# schematics.net
KiCad netlist of a schematic drawn in EasyEDA
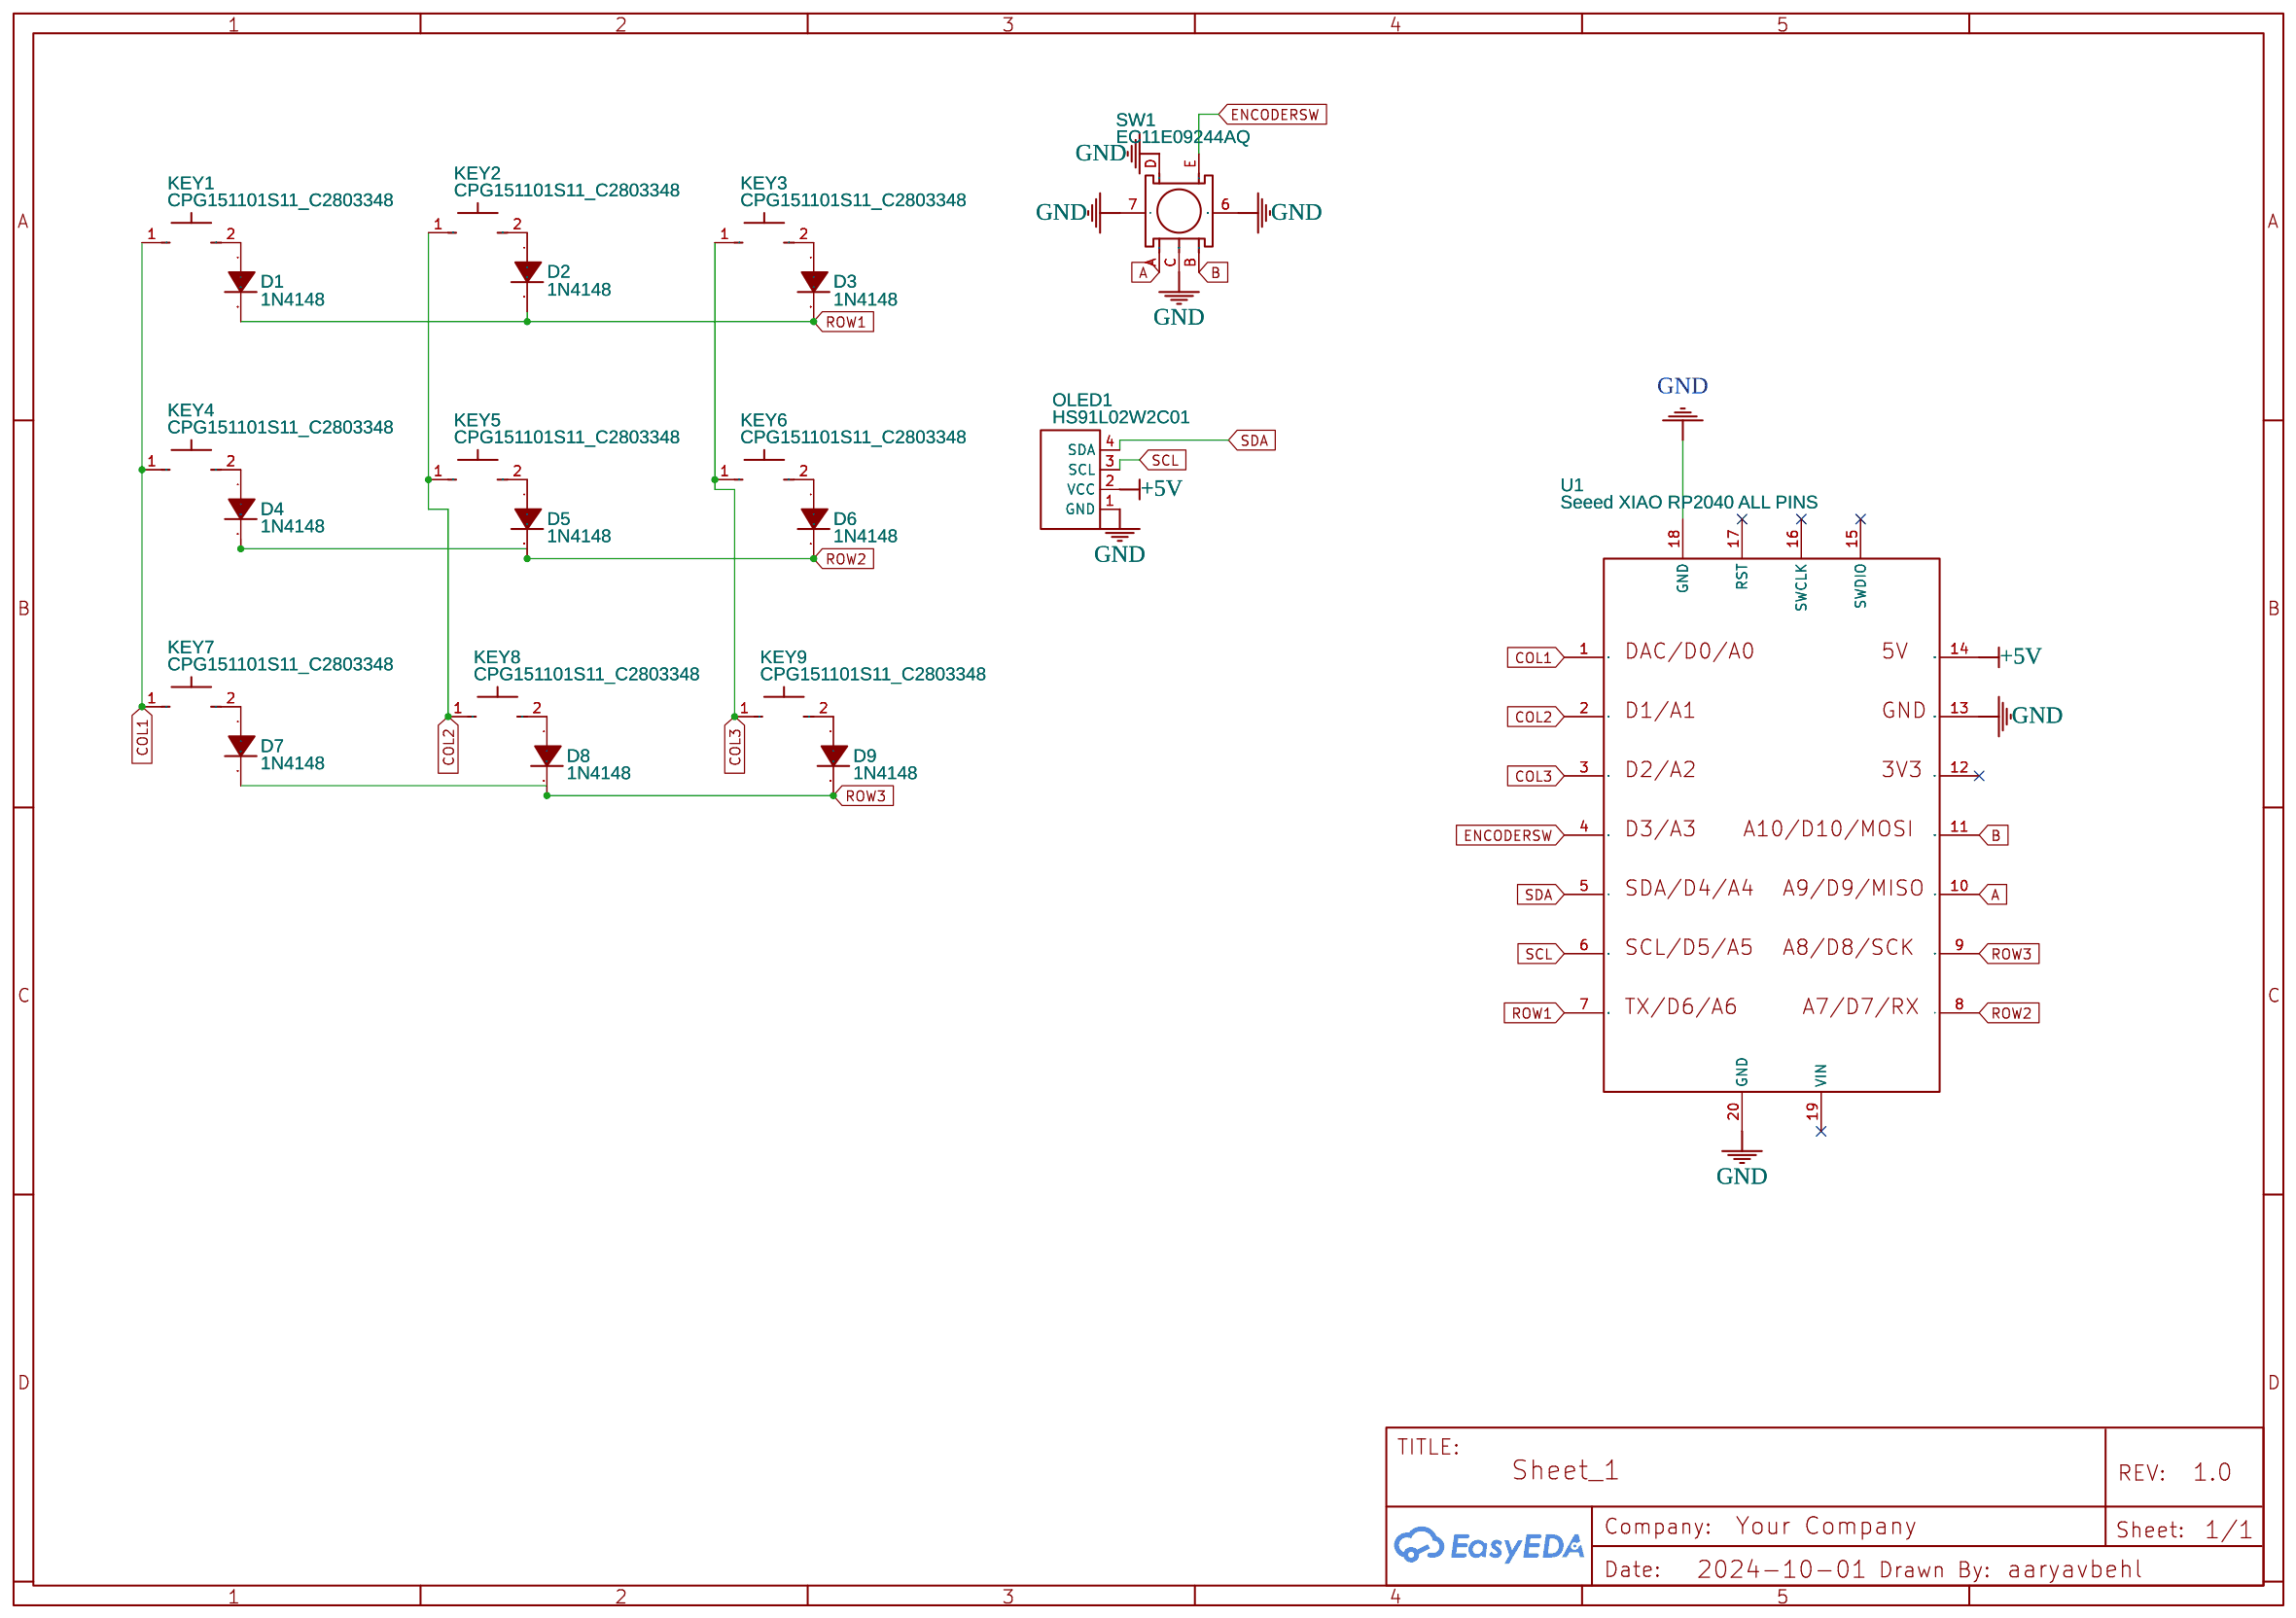
[diagram p0: schematic sheet]

(export (version "E")
  (design (tool "Eeschema 10.0.6"))
  (components
    (comp (ref "D1")
      (value "1N4148")
      (fields (field (name "Manufacturer") "ST(先科)"))
      (libsource (lib "") (part "1N4148"))
    )
    (comp (ref "D2")
      (value "1N4148")
      (fields (field (name "Manufacturer") "ST(先科)"))
      (libsource (lib "") (part "1N4148"))
    )
    (comp (ref "D3")
      (value "1N4148")
      (fields (field (name "Manufacturer") "ST(先科)"))
      (libsource (lib "") (part "1N4148"))
    )
    (comp (ref "D4")
      (value "1N4148")
      (fields (field (name "Manufacturer") "ST(先科)"))
      (libsource (lib "") (part "1N4148"))
    )
    (comp (ref "D5")
      (value "1N4148")
      (fields (field (name "Manufacturer") "ST(先科)"))
      (libsource (lib "") (part "1N4148"))
    )
    (comp (ref "D6")
      (value "1N4148")
      (fields (field (name "Manufacturer") "ST(先科)"))
      (libsource (lib "") (part "1N4148"))
    )
    (comp (ref "D7")
      (value "1N4148")
      (fields (field (name "Manufacturer") "ST(先科)"))
      (libsource (lib "") (part "1N4148"))
    )
    (comp (ref "D8")
      (value "1N4148")
      (fields (field (name "Manufacturer") "ST(先科)"))
      (libsource (lib "") (part "1N4148"))
    )
    (comp (ref "D9")
      (value "1N4148")
      (fields (field (name "Manufacturer") "ST(先科)"))
      (libsource (lib "") (part "1N4148"))
    )
    (comp (ref "KEY1")
      (value "CPG151101S11_C2803348")
      (fields (field (name "Manufacturer Part") "CPG151101S11") (field (name "Manufacturer") "Kailh(凯华)"))
      (libsource (lib "") (part "CPG151101S11_C2803348"))
    )
    (comp (ref "KEY2")
      (value "CPG151101S11_C2803348")
      (fields (field (name "Manufacturer Part") "CPG151101S11") (field (name "Manufacturer") "Kailh(凯华)"))
      (libsource (lib "") (part "CPG151101S11_C2803348"))
    )
    (comp (ref "KEY3")
      (value "CPG151101S11_C2803348")
      (fields (field (name "Manufacturer Part") "CPG151101S11") (field (name "Manufacturer") "Kailh(凯华)"))
      (libsource (lib "") (part "CPG151101S11_C2803348"))
    )
    (comp (ref "KEY4")
      (value "CPG151101S11_C2803348")
      (fields (field (name "Manufacturer Part") "CPG151101S11") (field (name "Manufacturer") "Kailh(凯华)"))
      (libsource (lib "") (part "CPG151101S11_C2803348"))
    )
    (comp (ref "KEY5")
      (value "CPG151101S11_C2803348")
      (fields (field (name "Manufacturer Part") "CPG151101S11") (field (name "Manufacturer") "Kailh(凯华)"))
      (libsource (lib "") (part "CPG151101S11_C2803348"))
    )
    (comp (ref "KEY6")
      (value "CPG151101S11_C2803348")
      (fields (field (name "Manufacturer Part") "CPG151101S11") (field (name "Manufacturer") "Kailh(凯华)"))
      (libsource (lib "") (part "CPG151101S11_C2803348"))
    )
    (comp (ref "KEY7")
      (value "CPG151101S11_C2803348")
      (fields (field (name "Manufacturer Part") "CPG151101S11") (field (name "Manufacturer") "Kailh(凯华)"))
      (libsource (lib "") (part "CPG151101S11_C2803348"))
    )
    (comp (ref "KEY8")
      (value "CPG151101S11_C2803348")
      (fields (field (name "Manufacturer Part") "CPG151101S11") (field (name "Manufacturer") "Kailh(凯华)"))
      (libsource (lib "") (part "CPG151101S11_C2803348"))
    )
    (comp (ref "KEY9")
      (value "CPG151101S11_C2803348")
      (fields (field (name "Manufacturer Part") "CPG151101S11") (field (name "Manufacturer") "Kailh(凯华)"))
      (libsource (lib "") (part "CPG151101S11_C2803348"))
    )
    (comp (ref "OLED1")
      (value "HS91L02W2C01")
      (fields (field (name "Manufacturer") "HS(汉昇)"))
      (libsource (lib "") (part "HS91L02W2C01"))
    )
    (comp (ref "SW1")
      (value "EC11E09244AQ")
      (fields (field (name "Manufacturer") "ALPSALPINE(阿尔卑斯阿尔派)"))
      (libsource (lib "") (part "EC11E09244AQ"))
    )
    (comp (ref "U1")
      (value "Seeed XIAO RP2040 ALL PINS")
      (fields (field (name "Manufacturer Part") "102010328") (field (name "Manufacturer") "Seeedstudio"))
      (libsource (lib "") (part "Seeed XIAO RP2040 ALL PINS"))
    )
  )
  (nets
    (net (code "1") (name "+5V") (class "Default")
      (node (ref "OLED1") (pin "2") (pinfunction "VCC_2") (pintype "unspecified"))
      (node (ref "U1") (pin "14") (pinfunction "13_14") (pintype "unspecified"))
    )
    (net (code "2") (name "A") (class "Default")
      (node (ref "SW1") (pin "A") (pinfunction "A_A") (pintype "unspecified"))
      (node (ref "U1") (pin "10") (pinfunction "9_10") (pintype "unspecified"))
    )
    (net (code "3") (name "B") (class "Default")
      (node (ref "SW1") (pin "B") (pinfunction "B_B") (pintype "unspecified"))
      (node (ref "U1") (pin "11") (pinfunction "10_11") (pintype "unspecified"))
    )
    (net (code "4") (name "COL1") (class "Default")
      (node (ref "KEY1") (pin "1") (pinfunction "1_1") (pintype "input"))
      (node (ref "KEY4") (pin "1") (pinfunction "1_1") (pintype "input"))
      (node (ref "KEY7") (pin "1") (pinfunction "1_1") (pintype "input"))
      (node (ref "U1") (pin "1") (pinfunction "0_1") (pintype "unspecified"))
    )
    (net (code "5") (name "COL2") (class "Default")
      (node (ref "KEY2") (pin "1") (pinfunction "1_1") (pintype "input"))
      (node (ref "KEY5") (pin "1") (pinfunction "1_1") (pintype "input"))
      (node (ref "KEY8") (pin "1") (pinfunction "1_1") (pintype "input"))
      (node (ref "U1") (pin "2") (pinfunction "1_2") (pintype "unspecified"))
    )
    (net (code "6") (name "COL3") (class "Default")
      (node (ref "KEY3") (pin "1") (pinfunction "1_1") (pintype "input"))
      (node (ref "KEY6") (pin "1") (pinfunction "1_1") (pintype "input"))
      (node (ref "KEY9") (pin "1") (pinfunction "1_1") (pintype "input"))
      (node (ref "U1") (pin "3") (pinfunction "2_3") (pintype "unspecified"))
    )
    (net (code "7") (name "ENCODERSW") (class "Default")
      (node (ref "SW1") (pin "E") (pinfunction "E_E") (pintype "unspecified"))
      (node (ref "U1") (pin "4") (pinfunction "3_4") (pintype "unspecified"))
    )
    (net (code "8") (name "GND") (class "Default")
      (node (ref "OLED1") (pin "1") (pinfunction "GND_1") (pintype "unspecified"))
      (node (ref "SW1") (pin "6") (pinfunction "6_6") (pintype "unspecified"))
      (node (ref "SW1") (pin "7") (pinfunction "7_7") (pintype "unspecified"))
      (node (ref "SW1") (pin "C") (pinfunction "C_C") (pintype "unspecified"))
      (node (ref "SW1") (pin "D") (pinfunction "D_D") (pintype "unspecified"))
      (node (ref "U1") (pin "13") (pinfunction "12_13") (pintype "unspecified"))
      (node (ref "U1") (pin "18") (pinfunction "GND_18") (pintype "unspecified"))
      (node (ref "U1") (pin "20") (pinfunction "GND_20") (pintype "unspecified"))
    )
    (net (code "9") (name "Net-(D1-A)") (class "Default")
      (node (ref "D1") (pin "1") (pinfunction "A_1") (pintype "unspecified"))
      (node (ref "KEY1") (pin "2") (pinfunction "2_2") (pintype "input"))
    )
    (net (code "10") (name "Net-(D2-A)") (class "Default")
      (node (ref "D2") (pin "1") (pinfunction "A_1") (pintype "unspecified"))
      (node (ref "KEY2") (pin "2") (pinfunction "2_2") (pintype "input"))
    )
    (net (code "11") (name "Net-(D3-A)") (class "Default")
      (node (ref "D3") (pin "1") (pinfunction "A_1") (pintype "unspecified"))
      (node (ref "KEY3") (pin "2") (pinfunction "2_2") (pintype "input"))
    )
    (net (code "12") (name "Net-(D4-A)") (class "Default")
      (node (ref "D4") (pin "1") (pinfunction "A_1") (pintype "unspecified"))
      (node (ref "KEY4") (pin "2") (pinfunction "2_2") (pintype "input"))
    )
    (net (code "13") (name "Net-(D5-A)") (class "Default")
      (node (ref "D5") (pin "1") (pinfunction "A_1") (pintype "unspecified"))
      (node (ref "KEY5") (pin "2") (pinfunction "2_2") (pintype "input"))
    )
    (net (code "14") (name "Net-(D6-A)") (class "Default")
      (node (ref "D6") (pin "1") (pinfunction "A_1") (pintype "unspecified"))
      (node (ref "KEY6") (pin "2") (pinfunction "2_2") (pintype "input"))
    )
    (net (code "15") (name "Net-(D7-A)") (class "Default")
      (node (ref "D7") (pin "1") (pinfunction "A_1") (pintype "unspecified"))
      (node (ref "KEY7") (pin "2") (pinfunction "2_2") (pintype "input"))
    )
    (net (code "16") (name "Net-(D8-A)") (class "Default")
      (node (ref "D8") (pin "1") (pinfunction "A_1") (pintype "unspecified"))
      (node (ref "KEY8") (pin "2") (pinfunction "2_2") (pintype "input"))
    )
    (net (code "17") (name "Net-(D9-A)") (class "Default")
      (node (ref "D9") (pin "1") (pinfunction "A_1") (pintype "unspecified"))
      (node (ref "KEY9") (pin "2") (pinfunction "2_2") (pintype "input"))
    )
    (net (code "18") (name "ROW1") (class "Default")
      (node (ref "D1") (pin "2") (pinfunction "C_2") (pintype "unspecified"))
      (node (ref "D2") (pin "2") (pinfunction "C_2") (pintype "unspecified"))
      (node (ref "D3") (pin "2") (pinfunction "C_2") (pintype "unspecified"))
      (node (ref "U1") (pin "7") (pinfunction "6_7") (pintype "unspecified"))
    )
    (net (code "19") (name "ROW2") (class "Default")
      (node (ref "D4") (pin "2") (pinfunction "C_2") (pintype "unspecified"))
      (node (ref "D5") (pin "2") (pinfunction "C_2") (pintype "unspecified"))
      (node (ref "D6") (pin "2") (pinfunction "C_2") (pintype "unspecified"))
      (node (ref "U1") (pin "8") (pinfunction "7_8") (pintype "unspecified"))
    )
    (net (code "20") (name "ROW3") (class "Default")
      (node (ref "D7") (pin "2") (pinfunction "C_2") (pintype "unspecified"))
      (node (ref "D8") (pin "2") (pinfunction "C_2") (pintype "unspecified"))
      (node (ref "D9") (pin "2") (pinfunction "C_2") (pintype "unspecified"))
      (node (ref "U1") (pin "9") (pinfunction "8_9") (pintype "unspecified"))
    )
    (net (code "21") (name "SCL") (class "Default")
      (node (ref "OLED1") (pin "3") (pinfunction "SCL_3") (pintype "unspecified"))
      (node (ref "U1") (pin "6") (pinfunction "5_6") (pintype "unspecified"))
    )
    (net (code "22") (name "SDA") (class "Default")
      (node (ref "OLED1") (pin "4") (pinfunction "SDA_4") (pintype "unspecified"))
      (node (ref "U1") (pin "5") (pinfunction "4_5") (pintype "unspecified"))
    )
    (net (code "23") (name "unconnected-(U1-11-Pad12)") (class "Default")
      (node (ref "U1") (pin "12") (pinfunction "11_12") (pintype "unspecified+no_connect"))
    )
    (net (code "24") (name "unconnected-(U1-RST-Pad17)") (class "Default")
      (node (ref "U1") (pin "17") (pinfunction "RST_17") (pintype "unspecified+no_connect"))
    )
    (net (code "25") (name "unconnected-(U1-SWCLK-Pad16)") (class "Default")
      (node (ref "U1") (pin "16") (pinfunction "SWCLK_16") (pintype "unspecified+no_connect"))
    )
    (net (code "26") (name "unconnected-(U1-SWDIO-Pad15)") (class "Default")
      (node (ref "U1") (pin "15") (pinfunction "SWDIO_15") (pintype "unspecified+no_connect"))
    )
    (net (code "27") (name "unconnected-(U1-VIN-Pad19)") (class "Default")
      (node (ref "U1") (pin "19") (pinfunction "VIN_19") (pintype "unspecified+no_connect"))
    )
  )
)
